# DevBoard.net
KiCad netlist of a schematic drawn in EAGLE
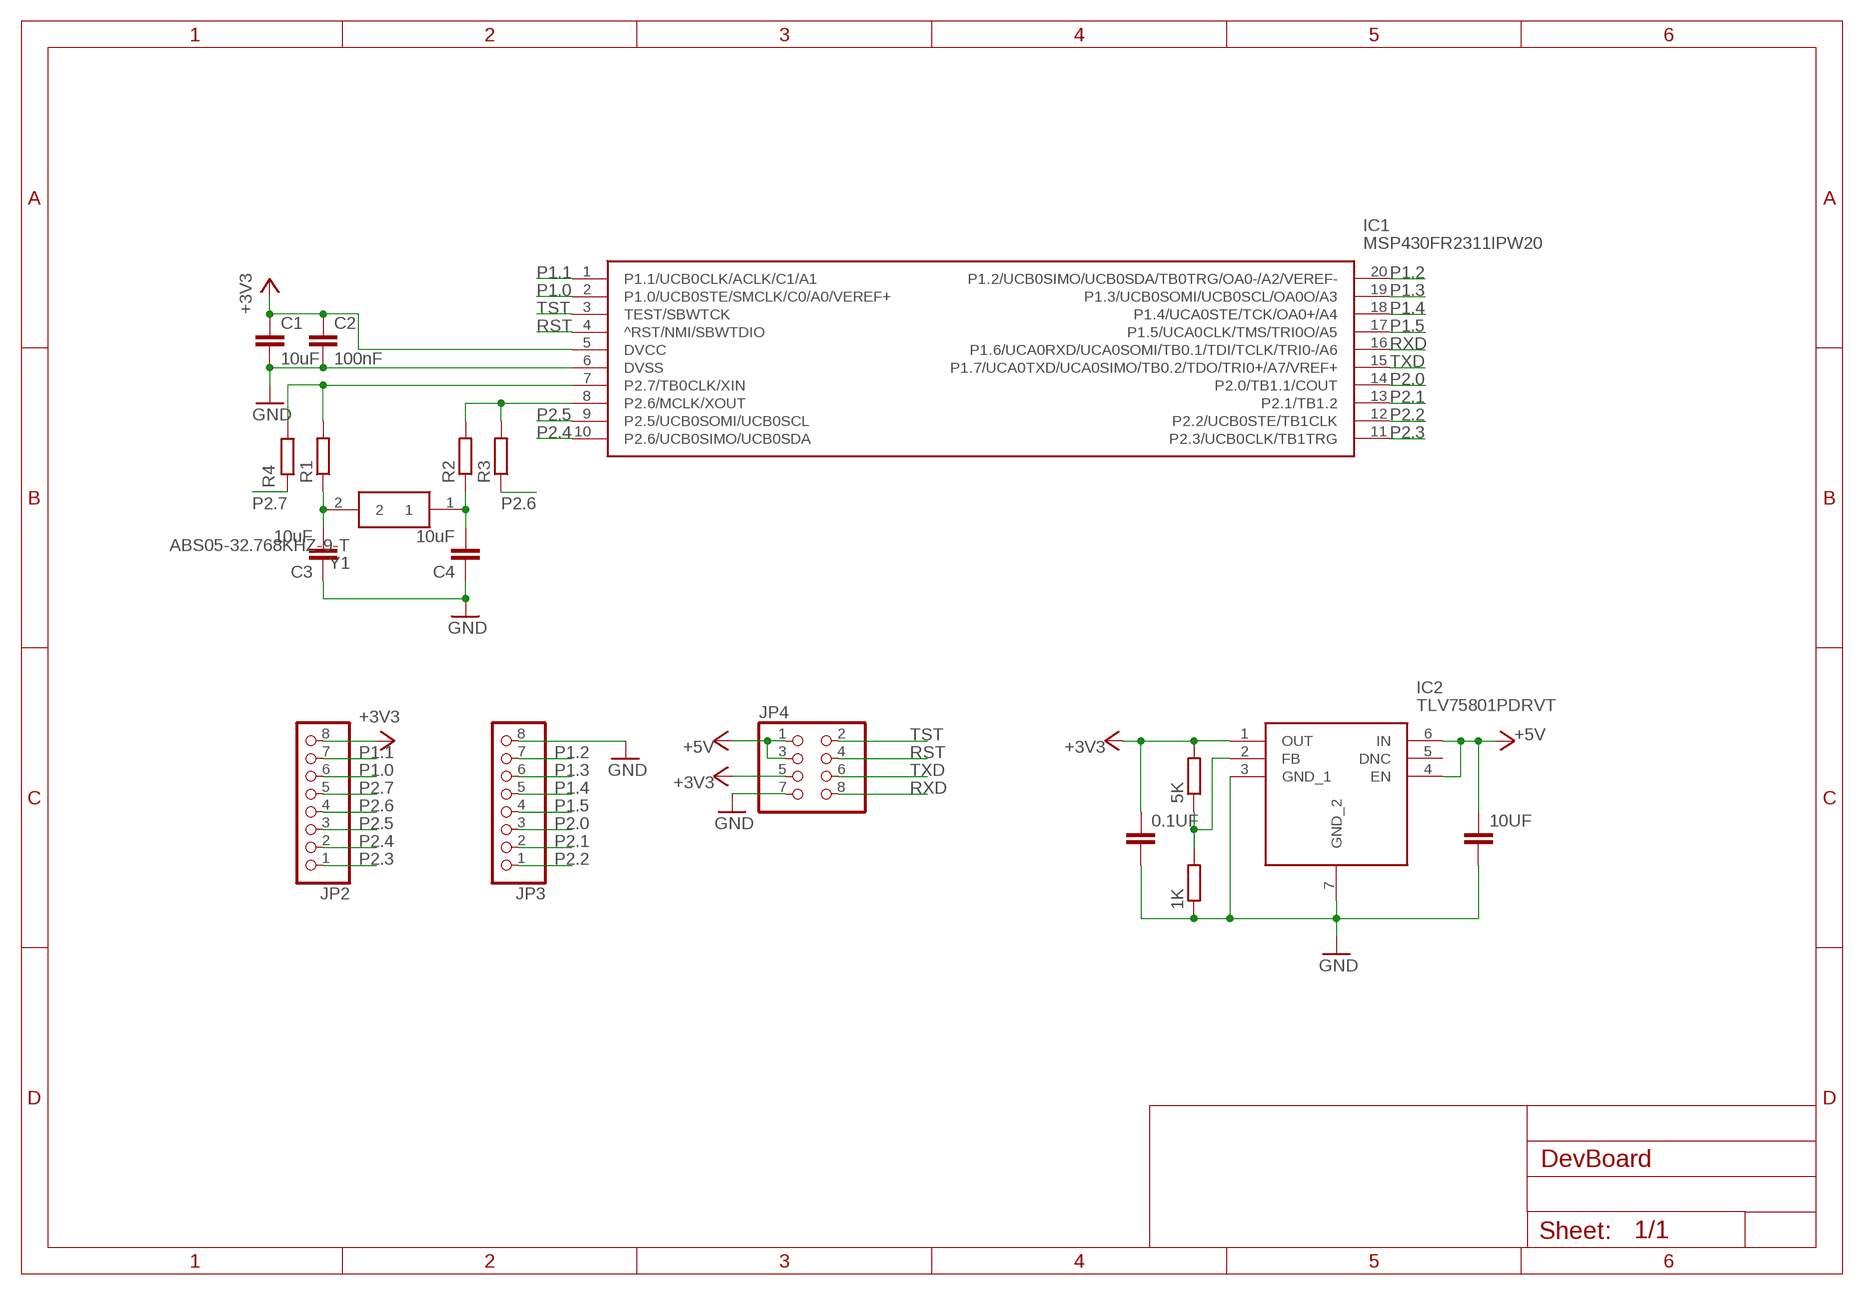
[diagram p0: schematic, sheet 1]

(export (version "E")
  (design (tool "Eeschema 10.0.6"))
  (components
    (comp (ref "0.1UF")
      (value "C-EUC0805K")
      (footprint "eagle-import:C0805K")
      (libsource (lib "eagle-import") (part "C-EUC0805K"))
    )
    (comp (ref "1K")
      (value "R-EU_R0805")
      (footprint "eagle-import:R0805")
      (libsource (lib "eagle-import") (part "R-EU_R0805"))
    )
    (comp (ref "5K")
      (value "R-EU_R0805")
      (footprint "eagle-import:R0805")
      (libsource (lib "eagle-import") (part "R-EU_R0805"))
    )
    (comp (ref "10UF")
      (value "C-EUC0805K")
      (footprint "eagle-import:C0805K")
      (libsource (lib "eagle-import") (part "C-EUC0805K"))
    )
    (comp (ref "C1")
      (value "10uF")
      (footprint "eagle-import:C0805K")
      (libsource (lib "eagle-import") (part "C-EUC0805K"))
    )
    (comp (ref "C2")
      (value "100nF")
      (footprint "eagle-import:C0805K")
      (libsource (lib "eagle-import") (part "C-EUC0805K"))
    )
    (comp (ref "C3")
      (value "10uF")
      (footprint "eagle-import:C0805K")
      (libsource (lib "eagle-import") (part "C-EUC0805K"))
    )
    (comp (ref "C4")
      (value "10uF")
      (footprint "eagle-import:C0805K")
      (libsource (lib "eagle-import") (part "C-EUC0805K"))
    )
    (comp (ref "IC1")
      (value "MSP430FR2311IPW20")
      (footprint "eagle-import:SOP65P640X120-20N")
      (fields (field (name "MOUSER_PART_NUMBER") "595-SP430FR2311IPW20"))
      (libsource (lib "eagle-import") (part "MSP430FR2311IPW20"))
    )
    (comp (ref "IC2")
      (value "TLV75801PDRVT")
      (footprint "eagle-import:SON65P200X200X80-7N")
      (fields (field (name "MOUSER_PART_NUMBER") "595-TLV75801PDRVT"))
      (libsource (lib "eagle-import") (part "TLV75801PDRVT"))
    )
    (comp (ref "JP2")
      (value "PINHD-1X8")
      (footprint "eagle-import:1X08")
      (libsource (lib "eagle-import") (part "PINHD-1X8"))
    )
    (comp (ref "JP3")
      (value "PINHD-1X8")
      (footprint "eagle-import:1X08")
      (libsource (lib "eagle-import") (part "PINHD-1X8"))
    )
    (comp (ref "JP4")
      (value "PINHD-2X4")
      (footprint "eagle-import:2X04")
      (libsource (lib "eagle-import") (part "PINHD-2X4"))
    )
    (comp (ref "R1")
      (value "R-EU_R0402")
      (footprint "eagle-import:R0402")
      (libsource (lib "eagle-import") (part "R-EU_R0402"))
    )
    (comp (ref "R2")
      (value "R-EU_R0402")
      (footprint "eagle-import:R0402")
      (libsource (lib "eagle-import") (part "R-EU_R0402"))
    )
    (comp (ref "R3")
      (value "R-EU_R0402")
      (footprint "eagle-import:R0402")
      (libsource (lib "eagle-import") (part "R-EU_R0402"))
    )
    (comp (ref "R4")
      (value "R-EU_R0402")
      (footprint "eagle-import:R0402")
      (libsource (lib "eagle-import") (part "R-EU_R0402"))
    )
    (comp (ref "Y1")
      (value "ABS05-32.768KHZ-9-T")
      (footprint "eagle-import:ABS05")
      (fields (field (name "MOUSER_PART_NUMBER") "815-ABS05-32.768K9T"))
      (libsource (lib "eagle-import") (part "ABS05-32.768KHZ-9-T"))
    )
  )
  (nets
    (net (code "1") (name "+3V3") (class "Default")
      (node (ref "0.1UF") (pin "1") (pinfunction "1_1") (pintype "passive"))
      (node (ref "5K") (pin "2") (pinfunction "2_2") (pintype "passive"))
      (node (ref "C1") (pin "1") (pinfunction "1_1") (pintype "passive"))
      (node (ref "C2") (pin "1") (pinfunction "1_1") (pintype "passive"))
      (node (ref "IC1") (pin "5") (pinfunction "DVCC_5") (pintype "power_in"))
      (node (ref "IC2") (pin "1") (pinfunction "OUT_1") (pintype "bidirectional"))
      (node (ref "JP2") (pin "8") (pinfunction "8_8") (pintype "passive"))
      (node (ref "JP4") (pin "5") (pinfunction "5_5") (pintype "passive"))
    )
    (net (code "2") (name "+5V") (class "Default")
      (node (ref "10UF") (pin "1") (pinfunction "1_1") (pintype "passive"))
      (node (ref "IC2") (pin "4") (pinfunction "EN_4") (pintype "bidirectional"))
      (node (ref "IC2") (pin "6") (pinfunction "IN_6") (pintype "bidirectional"))
      (node (ref "JP4") (pin "1") (pinfunction "1_1") (pintype "passive"))
      (node (ref "JP4") (pin "3") (pinfunction "3_3") (pintype "passive"))
    )
    (net (code "3") (name "/P1.0") (class "Default")
      (node (ref "IC1") (pin "2") (pinfunction "P1.0/UCB0STE/SMCLK/C0/A0/VEREF+_2") (pintype "bidirectional"))
      (node (ref "JP2") (pin "6") (pinfunction "6_6") (pintype "passive"))
    )
    (net (code "4") (name "/P1.1") (class "Default")
      (node (ref "IC1") (pin "1") (pinfunction "P1.1/UCB0CLK/ACLK/C1/A1_1") (pintype "bidirectional"))
      (node (ref "JP2") (pin "7") (pinfunction "7_7") (pintype "passive"))
    )
    (net (code "5") (name "/P1.2") (class "Default")
      (node (ref "IC1") (pin "20") (pinfunction "P1.2/UCB0SIMO/UCB0SDA/TB0TRG/OA0-/A2/VEREF-_20") (pintype "bidirectional"))
      (node (ref "JP3") (pin "7") (pinfunction "7_7") (pintype "passive"))
    )
    (net (code "6") (name "/P1.3") (class "Default")
      (node (ref "IC1") (pin "19") (pinfunction "P1.3/UCB0SOMI/UCB0SCL/OA0O/A3_19") (pintype "bidirectional"))
      (node (ref "JP3") (pin "6") (pinfunction "6_6") (pintype "passive"))
    )
    (net (code "7") (name "/P1.4") (class "Default")
      (node (ref "IC1") (pin "18") (pinfunction "P1.4/UCA0STE/TCK/OA0+/A4_18") (pintype "bidirectional"))
      (node (ref "JP3") (pin "5") (pinfunction "5_5") (pintype "passive"))
    )
    (net (code "8") (name "/P1.5") (class "Default")
      (node (ref "IC1") (pin "17") (pinfunction "P1.5/UCA0CLK/TMS/TRI0O/A5_17") (pintype "bidirectional"))
      (node (ref "JP3") (pin "4") (pinfunction "4_4") (pintype "passive"))
    )
    (net (code "9") (name "/P2.0") (class "Default")
      (node (ref "IC1") (pin "14") (pinfunction "P2.0/TB1.1/COUT_14") (pintype "bidirectional"))
      (node (ref "JP3") (pin "3") (pinfunction "3_3") (pintype "passive"))
    )
    (net (code "10") (name "/P2.1") (class "Default")
      (node (ref "IC1") (pin "13") (pinfunction "P2.1/TB1.2_13") (pintype "bidirectional"))
      (node (ref "JP3") (pin "2") (pinfunction "2_2") (pintype "passive"))
    )
    (net (code "11") (name "/P2.2") (class "Default")
      (node (ref "IC1") (pin "12") (pinfunction "P2.2/UCB0STE/TB1CLK_12") (pintype "bidirectional"))
      (node (ref "JP3") (pin "1") (pinfunction "1_1") (pintype "passive"))
    )
    (net (code "12") (name "/P2.3") (class "Default")
      (node (ref "IC1") (pin "11") (pinfunction "P2.3/UCB0CLK/TB1TRG_11") (pintype "bidirectional"))
      (node (ref "JP2") (pin "1") (pinfunction "1_1") (pintype "passive"))
    )
    (net (code "13") (name "/P2.4") (class "Default")
      (node (ref "IC1") (pin "10") (pinfunction "P2.6/UCB0SIMO/UCB0SDA_10") (pintype "bidirectional"))
      (node (ref "JP2") (pin "2") (pinfunction "2_2") (pintype "passive"))
    )
    (net (code "14") (name "/P2.5") (class "Default")
      (node (ref "IC1") (pin "9") (pinfunction "P2.5/UCB0SOMI/UCB0SCL_9") (pintype "bidirectional"))
      (node (ref "JP2") (pin "3") (pinfunction "3_3") (pintype "passive"))
    )
    (net (code "15") (name "/P2.6") (class "Default")
      (node (ref "JP2") (pin "4") (pinfunction "4_4") (pintype "passive"))
      (node (ref "R3") (pin "1") (pinfunction "1_1") (pintype "passive"))
    )
    (net (code "16") (name "/P2.7") (class "Default")
      (node (ref "JP2") (pin "5") (pinfunction "5_5") (pintype "passive"))
      (node (ref "R4") (pin "2") (pinfunction "2_2") (pintype "passive"))
    )
    (net (code "17") (name "/RST") (class "Default")
      (node (ref "IC1") (pin "4") (pinfunction "^RST/NMI/SBWTDIO_4") (pintype "bidirectional"))
      (node (ref "JP4") (pin "4") (pinfunction "4_4") (pintype "passive"))
    )
    (net (code "18") (name "/RXD") (class "Default")
      (node (ref "IC1") (pin "16") (pinfunction "P1.6/UCA0RXD/UCA0SOMI/TB0.1/TDI/TCLK/TRI0-/A6_16") (pintype "bidirectional"))
      (node (ref "JP4") (pin "8") (pinfunction "8_8") (pintype "passive"))
    )
    (net (code "19") (name "/TST") (class "Default")
      (node (ref "IC1") (pin "3") (pinfunction "TEST/SBWTCK_3") (pintype "bidirectional"))
      (node (ref "JP4") (pin "2") (pinfunction "2_2") (pintype "passive"))
    )
    (net (code "20") (name "/TXD") (class "Default")
      (node (ref "IC1") (pin "15") (pinfunction "P1.7/UCA0TXD/UCA0SIMO/TB0.2/TDO/TRI0+/A7/VREF+_15") (pintype "bidirectional"))
      (node (ref "JP4") (pin "6") (pinfunction "6_6") (pintype "passive"))
    )
    (net (code "21") (name "GND") (class "Default")
      (node (ref "0.1UF") (pin "2") (pinfunction "2_2") (pintype "passive"))
      (node (ref "10UF") (pin "2") (pinfunction "2_2") (pintype "passive"))
      (node (ref "1K") (pin "1") (pinfunction "1_1") (pintype "passive"))
      (node (ref "C1") (pin "2") (pinfunction "2_2") (pintype "passive"))
      (node (ref "C2") (pin "2") (pinfunction "2_2") (pintype "passive"))
      (node (ref "C3") (pin "1") (pinfunction "1_1") (pintype "passive"))
      (node (ref "C4") (pin "1") (pinfunction "1_1") (pintype "passive"))
      (node (ref "IC1") (pin "6") (pinfunction "DVSS_6") (pintype "power_in"))
      (node (ref "IC2") (pin "3") (pinfunction "GND_1_3") (pintype "bidirectional"))
      (node (ref "IC2") (pin "7") (pinfunction "GND_2_7") (pintype "bidirectional"))
      (node (ref "JP3") (pin "8") (pinfunction "8_8") (pintype "passive"))
      (node (ref "JP4") (pin "7") (pinfunction "7_7") (pintype "passive"))
    )
    (net (code "22") (name "Net-(C3-Pad2)") (class "Default")
      (node (ref "C3") (pin "2") (pinfunction "2_2") (pintype "passive"))
      (node (ref "R1") (pin "1") (pinfunction "1_1") (pintype "passive"))
      (node (ref "Y1") (pin "2") (pinfunction "2_2") (pintype "bidirectional"))
    )
    (net (code "23") (name "Net-(C4-Pad2)") (class "Default")
      (node (ref "C4") (pin "2") (pinfunction "2_2") (pintype "passive"))
      (node (ref "R2") (pin "1") (pinfunction "1_1") (pintype "passive"))
      (node (ref "Y1") (pin "1") (pinfunction "1_1") (pintype "bidirectional"))
    )
    (net (code "24") (name "Net-(IC1-P2.6{slash}MCLK{slash}XOUT)") (class "Default")
      (node (ref "IC1") (pin "8") (pinfunction "P2.6/MCLK/XOUT_8") (pintype "bidirectional"))
      (node (ref "R2") (pin "2") (pinfunction "2_2") (pintype "passive"))
      (node (ref "R3") (pin "2") (pinfunction "2_2") (pintype "passive"))
    )
    (net (code "25") (name "Net-(IC1-P2.7{slash}TB0CLK{slash}XIN)") (class "Default")
      (node (ref "IC1") (pin "7") (pinfunction "P2.7/TB0CLK/XIN_7") (pintype "bidirectional"))
      (node (ref "R1") (pin "2") (pinfunction "2_2") (pintype "passive"))
      (node (ref "R4") (pin "1") (pinfunction "1_1") (pintype "passive"))
    )
    (net (code "26") (name "Net-(IC2-FB)") (class "Default")
      (node (ref "1K") (pin "2") (pinfunction "2_2") (pintype "passive"))
      (node (ref "5K") (pin "1") (pinfunction "1_1") (pintype "passive"))
      (node (ref "IC2") (pin "2") (pinfunction "FB_2") (pintype "bidirectional"))
    )
    (net (code "27") (name "unconnected-(IC2-DNC-Pad5)") (class "Default")
      (node (ref "IC2") (pin "5") (pinfunction "DNC_5") (pintype "bidirectional"))
    )
  )
)
